# G228H.net
KiCad netlist of a schematic drawn in EAGLE
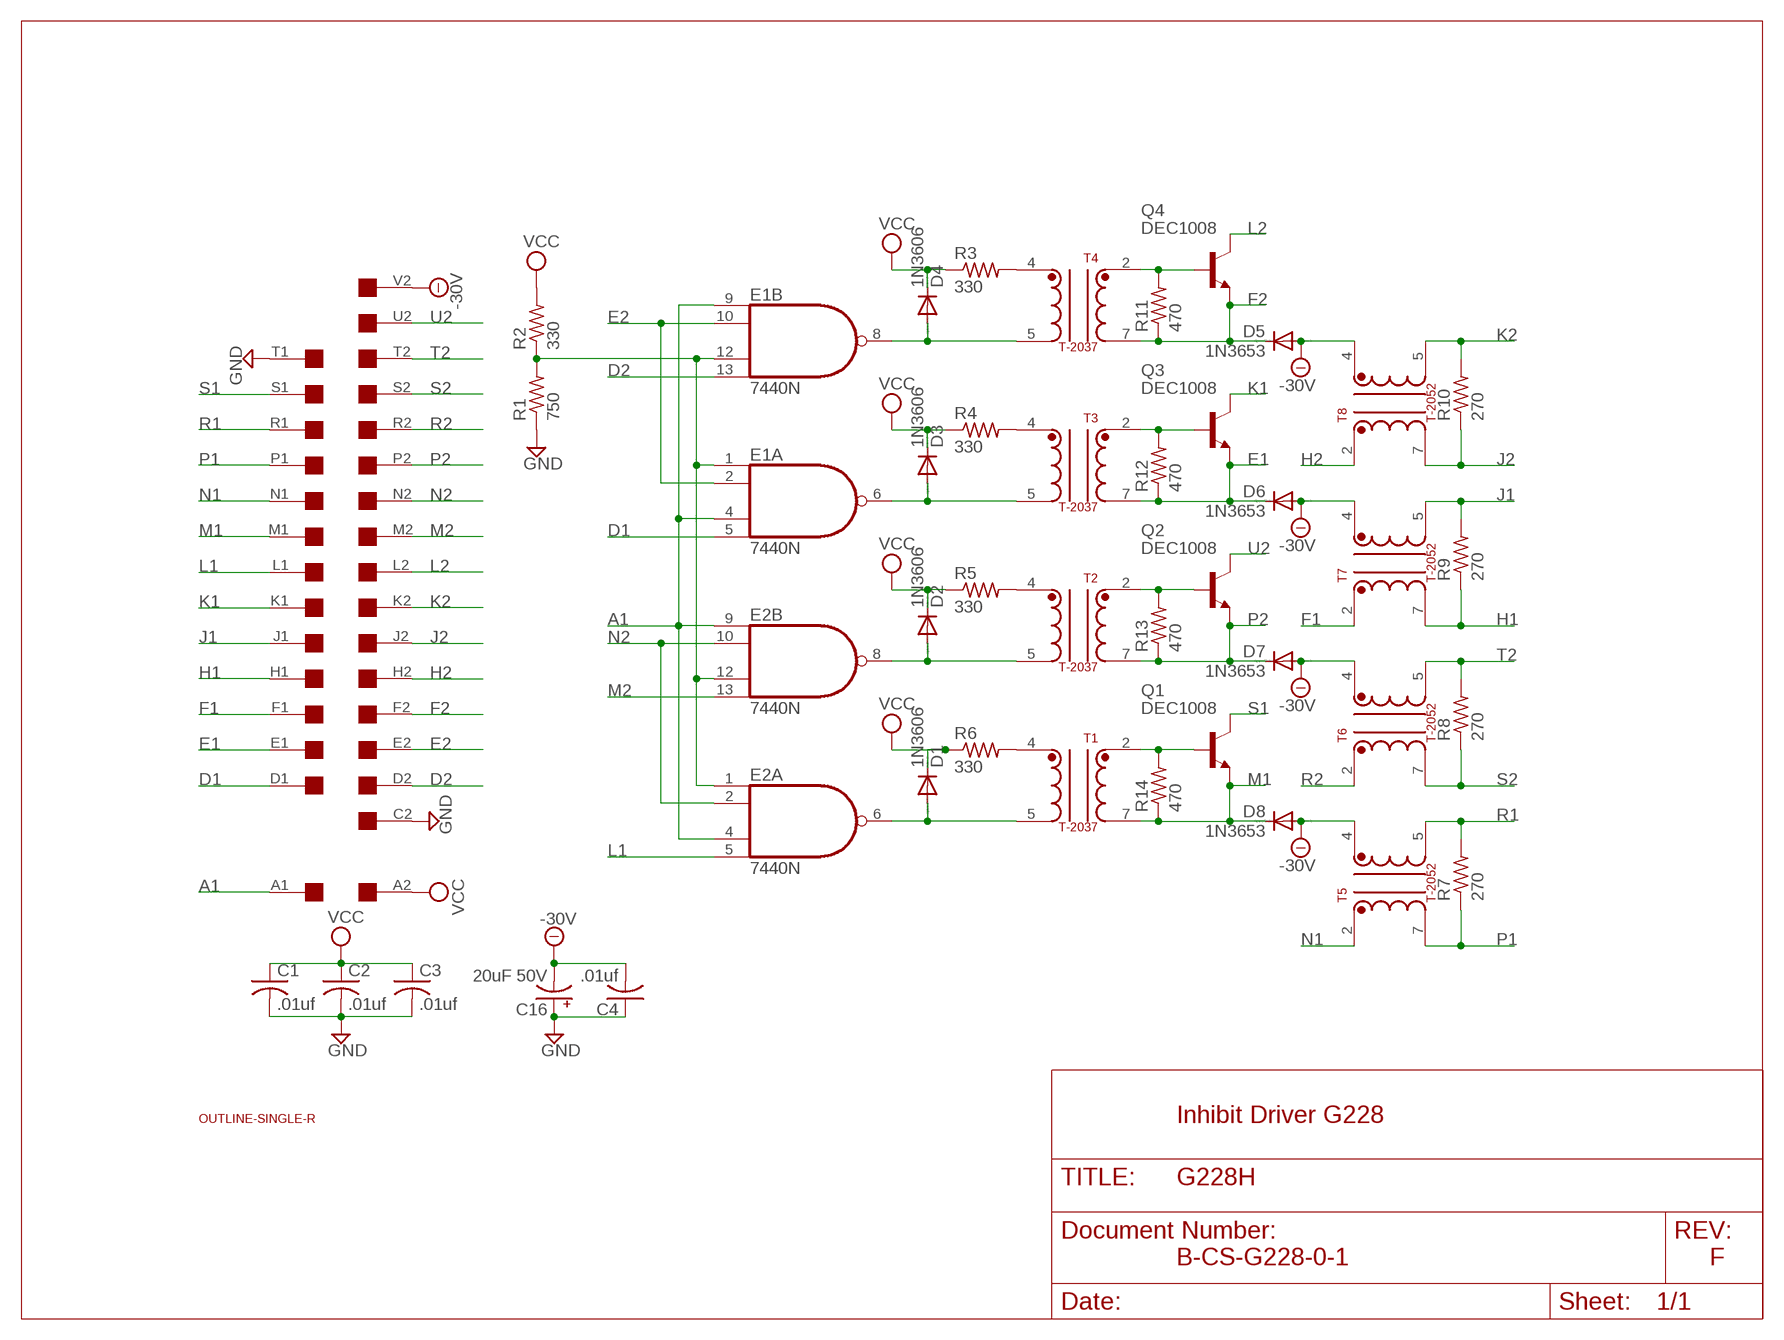
[diagram p0: schematic, sheet 1]

(export (version "E")
  (design (tool "Eeschema 10.0.6"))
  (components
    (comp (ref "C1")
      (value ".01uf")
      (footprint "eagle-import:C050-025X075")
      (libsource (lib "eagle-import") (part "C-US050-025X075"))
    )
    (comp (ref "C2")
      (value ".01uf")
      (footprint "eagle-import:C050-025X075")
      (libsource (lib "eagle-import") (part "C-US050-025X075"))
    )
    (comp (ref "C3")
      (value ".01uf")
      (footprint "eagle-import:C050-025X075")
      (libsource (lib "eagle-import") (part "C-US050-025X075"))
    )
    (comp (ref "C4")
      (value ".01uf")
      (footprint "eagle-import:C050-025X075")
      (libsource (lib "eagle-import") (part "C-US050-025X075"))
    )
    (comp (ref "C16")
      (value "20uF 50V")
      (footprint "eagle-import:E28-8")
      (libsource (lib "eagle-import") (part "CPOL-USE28-8AXIAL"))
    )
    (comp (ref "D1")
      (value "1N3606")
      (footprint "eagle-import:DO35-10")
      (libsource (lib "eagle-import") (part "1N4148DO35-10"))
    )
    (comp (ref "D2")
      (value "1N3606")
      (footprint "eagle-import:DO35-10")
      (libsource (lib "eagle-import") (part "1N4148DO35-10"))
    )
    (comp (ref "D3")
      (value "1N3606")
      (footprint "eagle-import:DO35-10")
      (libsource (lib "eagle-import") (part "1N4148DO35-10"))
    )
    (comp (ref "D4")
      (value "1N3606")
      (footprint "eagle-import:DO35-10")
      (libsource (lib "eagle-import") (part "1N4148DO35-10"))
    )
    (comp (ref "D5")
      (value "1N3653")
      (footprint "eagle-import:DO35-10")
      (libsource (lib "eagle-import") (part "1N4148DO35-10"))
    )
    (comp (ref "D6")
      (value "1N3653")
      (footprint "eagle-import:DO35-10")
      (libsource (lib "eagle-import") (part "1N4148DO35-10"))
    )
    (comp (ref "D7")
      (value "1N3653")
      (footprint "eagle-import:DO35-10")
      (libsource (lib "eagle-import") (part "1N4148DO35-10"))
    )
    (comp (ref "D8")
      (value "1N3653")
      (footprint "eagle-import:DO35-10")
      (libsource (lib "eagle-import") (part "1N4148DO35-10"))
    )
    (comp (ref "E1")
      (value "7440N")
      (footprint "eagle-import:DIL14")
      (libsource (lib "eagle-import") (part "7420NS"))
    )
    (comp (ref "E2")
      (value "7440N")
      (footprint "eagle-import:DIL14")
      (libsource (lib "eagle-import") (part "7420NS"))
    )
    (comp (ref "Q1")
      (value "DEC1008")
      (footprint "eagle-import:TO39")
      (libsource (lib "eagle-import") (part "-NPN-TO39-EBC2N1613"))
    )
    (comp (ref "Q2")
      (value "DEC1008")
      (footprint "eagle-import:TO39")
      (libsource (lib "eagle-import") (part "-NPN-TO39-EBC2N1613"))
    )
    (comp (ref "Q3")
      (value "DEC1008")
      (footprint "eagle-import:TO39")
      (libsource (lib "eagle-import") (part "-NPN-TO39-EBC2N1613"))
    )
    (comp (ref "Q4")
      (value "DEC1008")
      (footprint "eagle-import:TO39")
      (libsource (lib "eagle-import") (part "-NPN-TO39-EBC2N1613"))
    )
    (comp (ref "R1")
      (value "750")
      (footprint "eagle-import:0207_10")
      (libsource (lib "eagle-import") (part "R-US_0207/10"))
    )
    (comp (ref "R2")
      (value "330")
      (footprint "eagle-import:0207_10")
      (libsource (lib "eagle-import") (part "R-US_0207/10"))
    )
    (comp (ref "R3")
      (value "330")
      (footprint "eagle-import:0207_10")
      (libsource (lib "eagle-import") (part "R-US_0207/10"))
    )
    (comp (ref "R4")
      (value "330")
      (footprint "eagle-import:0207_10")
      (libsource (lib "eagle-import") (part "R-US_0207/10"))
    )
    (comp (ref "R5")
      (value "330")
      (footprint "eagle-import:0207_10")
      (libsource (lib "eagle-import") (part "R-US_0207/10"))
    )
    (comp (ref "R6")
      (value "330")
      (footprint "eagle-import:0207_10")
      (libsource (lib "eagle-import") (part "R-US_0207/10"))
    )
    (comp (ref "R7")
      (value "270")
      (footprint "eagle-import:0207_10")
      (libsource (lib "eagle-import") (part "R-US_0207/10"))
    )
    (comp (ref "R8")
      (value "270")
      (footprint "eagle-import:0207_10")
      (libsource (lib "eagle-import") (part "R-US_0207/10"))
    )
    (comp (ref "R9")
      (value "270")
      (footprint "eagle-import:0207_10")
      (libsource (lib "eagle-import") (part "R-US_0207/10"))
    )
    (comp (ref "R10")
      (value "270")
      (footprint "eagle-import:0207_10")
      (libsource (lib "eagle-import") (part "R-US_0207/10"))
    )
    (comp (ref "R11")
      (value "470")
      (footprint "eagle-import:0207_10")
      (libsource (lib "eagle-import") (part "R-US_0207/10"))
    )
    (comp (ref "R12")
      (value "470")
      (footprint "eagle-import:0207_10")
      (libsource (lib "eagle-import") (part "R-US_0207/10"))
    )
    (comp (ref "R13")
      (value "470")
      (footprint "eagle-import:0207_10")
      (libsource (lib "eagle-import") (part "R-US_0207/10"))
    )
    (comp (ref "R14")
      (value "470")
      (footprint "eagle-import:0207_10")
      (libsource (lib "eagle-import") (part "R-US_0207/10"))
    )
    (comp (ref "T1")
      (value "T-2037")
      (footprint "eagle-import:TRANSFORMER")
      (libsource (lib "eagle-import") (part "T-2037"))
    )
    (comp (ref "T2")
      (value "T-2037")
      (footprint "eagle-import:TRANSFORMER")
      (libsource (lib "eagle-import") (part "T-2037"))
    )
    (comp (ref "T3")
      (value "T-2037")
      (footprint "eagle-import:TRANSFORMER")
      (libsource (lib "eagle-import") (part "T-2037"))
    )
    (comp (ref "T4")
      (value "T-2037")
      (footprint "eagle-import:TRANSFORMER")
      (libsource (lib "eagle-import") (part "T-2037"))
    )
    (comp (ref "T5")
      (value "T-2052")
      (footprint "eagle-import:TRANSFORMER")
      (libsource (lib "eagle-import") (part "T-2052"))
    )
    (comp (ref "T6")
      (value "T-2052")
      (footprint "eagle-import:TRANSFORMER")
      (libsource (lib "eagle-import") (part "T-2052"))
    )
    (comp (ref "T7")
      (value "T-2052")
      (footprint "eagle-import:TRANSFORMER")
      (libsource (lib "eagle-import") (part "T-2052"))
    )
    (comp (ref "T8")
      (value "T-2052")
      (footprint "eagle-import:TRANSFORMER")
      (libsource (lib "eagle-import") (part "T-2052"))
    )
    (comp (ref "U$1")
      (value "SINGLE")
      (footprint "eagle-import:EDGE-CON2")
      (libsource (lib "eagle-import") (part "SINGLE"))
    )
    (comp (ref "U$2")
      (value "OUTLINE-SINGLE-R")
      (footprint "eagle-import:SINGLE-R")
      (libsource (lib "eagle-import") (part "OUTLINE-SINGLE-R"))
    )
  )
  (nets
    (net (code "1") (name "-30V") (class "Default")
      (node (ref "C16") (pin "-") (pinfunction "-_-") (pintype "passive"))
      (node (ref "C4") (pin "2") (pinfunction "2_2") (pintype "passive"))
      (node (ref "D5") (pin "A") (pinfunction "A_A") (pintype "passive"))
      (node (ref "D6") (pin "A") (pinfunction "A_A") (pintype "passive"))
      (node (ref "D7") (pin "A") (pinfunction "A_A") (pintype "passive"))
      (node (ref "D8") (pin "A") (pinfunction "A_A") (pintype "passive"))
      (node (ref "T5") (pin "4") (pinfunction "P$4_4") (pintype "passive"))
      (node (ref "T6") (pin "4") (pinfunction "P$4_4") (pintype "passive"))
      (node (ref "T7") (pin "4") (pinfunction "P$4_4") (pintype "passive"))
      (node (ref "T8") (pin "4") (pinfunction "P$4_4") (pintype "passive"))
      (node (ref "U$1") (pin "V2") (pinfunction "1_V2") (pintype "bidirectional"))
    )
    (net (code "2") (name "/A1") (class "Default")
      (node (ref "E1") (pin "4") (pinfunction "I2_4") (pintype "input"))
      (node (ref "E1") (pin "9") (pinfunction "I0_9") (pintype "input"))
      (node (ref "E2") (pin "4") (pinfunction "I2_4") (pintype "input"))
      (node (ref "E2") (pin "9") (pinfunction "I0_9") (pintype "input"))
      (node (ref "U$1") (pin "A1") (pinfunction "1_A1") (pintype "bidirectional"))
    )
    (net (code "3") (name "/D1") (class "Default")
      (node (ref "E1") (pin "5") (pinfunction "I3_5") (pintype "input"))
      (node (ref "U$1") (pin "D1") (pinfunction "1_D1") (pintype "bidirectional"))
    )
    (net (code "4") (name "/D2") (class "Default")
      (node (ref "E1") (pin "13") (pinfunction "I3_13") (pintype "input"))
      (node (ref "U$1") (pin "D2") (pinfunction "1_D2") (pintype "bidirectional"))
    )
    (net (code "5") (name "/E1") (class "Default")
      (node (ref "D6") (pin "C") (pinfunction "C_C") (pintype "passive"))
      (node (ref "Q3") (pin "1") (pinfunction "E_1") (pintype "passive"))
      (node (ref "R12") (pin "1") (pinfunction "1_1") (pintype "passive"))
      (node (ref "T3") (pin "7") (pinfunction "P$7_7") (pintype "passive"))
      (node (ref "U$1") (pin "E1") (pinfunction "1_E1") (pintype "bidirectional"))
    )
    (net (code "6") (name "/E2") (class "Default")
      (node (ref "E1") (pin "10") (pinfunction "I1_10") (pintype "input"))
      (node (ref "E1") (pin "2") (pinfunction "I1_2") (pintype "input"))
      (node (ref "U$1") (pin "E2") (pinfunction "1_E2") (pintype "bidirectional"))
    )
    (net (code "7") (name "/F1") (class "Default")
      (node (ref "T7") (pin "2") (pinfunction "P$2_2") (pintype "passive"))
      (node (ref "U$1") (pin "F1") (pinfunction "1_F1") (pintype "bidirectional"))
    )
    (net (code "8") (name "/F2") (class "Default")
      (node (ref "D5") (pin "C") (pinfunction "C_C") (pintype "passive"))
      (node (ref "Q4") (pin "1") (pinfunction "E_1") (pintype "passive"))
      (node (ref "R11") (pin "1") (pinfunction "1_1") (pintype "passive"))
      (node (ref "T4") (pin "7") (pinfunction "P$7_7") (pintype "passive"))
      (node (ref "U$1") (pin "F2") (pinfunction "1_F2") (pintype "bidirectional"))
    )
    (net (code "9") (name "/H1") (class "Default")
      (node (ref "R9") (pin "1") (pinfunction "1_1") (pintype "passive"))
      (node (ref "T7") (pin "7") (pinfunction "P$7_7") (pintype "passive"))
      (node (ref "U$1") (pin "H1") (pinfunction "1_H1") (pintype "bidirectional"))
    )
    (net (code "10") (name "/H2") (class "Default")
      (node (ref "T8") (pin "2") (pinfunction "P$2_2") (pintype "passive"))
      (node (ref "U$1") (pin "H2") (pinfunction "1_H2") (pintype "bidirectional"))
    )
    (net (code "11") (name "/J1") (class "Default")
      (node (ref "R9") (pin "2") (pinfunction "2_2") (pintype "passive"))
      (node (ref "T7") (pin "5") (pinfunction "P$5_5") (pintype "passive"))
      (node (ref "U$1") (pin "J1") (pinfunction "1_J1") (pintype "bidirectional"))
    )
    (net (code "12") (name "/J2") (class "Default")
      (node (ref "R10") (pin "1") (pinfunction "1_1") (pintype "passive"))
      (node (ref "T8") (pin "7") (pinfunction "P$7_7") (pintype "passive"))
      (node (ref "U$1") (pin "J2") (pinfunction "1_J2") (pintype "bidirectional"))
    )
    (net (code "13") (name "/K1") (class "Default")
      (node (ref "Q3") (pin "3") (pinfunction "C_3") (pintype "passive"))
      (node (ref "U$1") (pin "K1") (pinfunction "1_K1") (pintype "bidirectional"))
    )
    (net (code "14") (name "/K2") (class "Default")
      (node (ref "R10") (pin "2") (pinfunction "2_2") (pintype "passive"))
      (node (ref "T8") (pin "5") (pinfunction "P$5_5") (pintype "passive"))
      (node (ref "U$1") (pin "K2") (pinfunction "1_K2") (pintype "bidirectional"))
    )
    (net (code "15") (name "/L1") (class "Default")
      (node (ref "E2") (pin "5") (pinfunction "I3_5") (pintype "input"))
      (node (ref "U$1") (pin "L1") (pinfunction "1_L1") (pintype "bidirectional"))
    )
    (net (code "16") (name "/L2") (class "Default")
      (node (ref "Q4") (pin "3") (pinfunction "C_3") (pintype "passive"))
      (node (ref "U$1") (pin "L2") (pinfunction "1_L2") (pintype "bidirectional"))
    )
    (net (code "17") (name "/M1") (class "Default")
      (node (ref "D8") (pin "C") (pinfunction "C_C") (pintype "passive"))
      (node (ref "Q1") (pin "1") (pinfunction "E_1") (pintype "passive"))
      (node (ref "R14") (pin "1") (pinfunction "1_1") (pintype "passive"))
      (node (ref "T1") (pin "7") (pinfunction "P$7_7") (pintype "passive"))
      (node (ref "U$1") (pin "M1") (pinfunction "1_M1") (pintype "bidirectional"))
    )
    (net (code "18") (name "/M2") (class "Default")
      (node (ref "E2") (pin "13") (pinfunction "I3_13") (pintype "input"))
      (node (ref "U$1") (pin "M2") (pinfunction "1_M2") (pintype "bidirectional"))
    )
    (net (code "19") (name "/N1") (class "Default")
      (node (ref "T5") (pin "2") (pinfunction "P$2_2") (pintype "passive"))
      (node (ref "U$1") (pin "N1") (pinfunction "1_N1") (pintype "bidirectional"))
    )
    (net (code "20") (name "/N2") (class "Default")
      (node (ref "E2") (pin "10") (pinfunction "I1_10") (pintype "input"))
      (node (ref "E2") (pin "2") (pinfunction "I1_2") (pintype "input"))
      (node (ref "U$1") (pin "N2") (pinfunction "1_N2") (pintype "bidirectional"))
    )
    (net (code "21") (name "/P1") (class "Default")
      (node (ref "R7") (pin "1") (pinfunction "1_1") (pintype "passive"))
      (node (ref "T5") (pin "7") (pinfunction "P$7_7") (pintype "passive"))
      (node (ref "U$1") (pin "P1") (pinfunction "1_P1") (pintype "bidirectional"))
    )
    (net (code "22") (name "/P2") (class "Default")
      (node (ref "D7") (pin "C") (pinfunction "C_C") (pintype "passive"))
      (node (ref "Q2") (pin "1") (pinfunction "E_1") (pintype "passive"))
      (node (ref "R13") (pin "1") (pinfunction "1_1") (pintype "passive"))
      (node (ref "T2") (pin "7") (pinfunction "P$7_7") (pintype "passive"))
      (node (ref "U$1") (pin "P2") (pinfunction "1_P2") (pintype "bidirectional"))
    )
    (net (code "23") (name "/R1") (class "Default")
      (node (ref "R7") (pin "2") (pinfunction "2_2") (pintype "passive"))
      (node (ref "T5") (pin "5") (pinfunction "P$5_5") (pintype "passive"))
      (node (ref "U$1") (pin "R1") (pinfunction "1_R1") (pintype "bidirectional"))
    )
    (net (code "24") (name "/R2") (class "Default")
      (node (ref "T6") (pin "2") (pinfunction "P$2_2") (pintype "passive"))
      (node (ref "U$1") (pin "R2") (pinfunction "1_R2") (pintype "bidirectional"))
    )
    (net (code "25") (name "/S1") (class "Default")
      (node (ref "Q1") (pin "3") (pinfunction "C_3") (pintype "passive"))
      (node (ref "U$1") (pin "S1") (pinfunction "1_S1") (pintype "bidirectional"))
    )
    (net (code "26") (name "/S2") (class "Default")
      (node (ref "R8") (pin "1") (pinfunction "1_1") (pintype "passive"))
      (node (ref "T6") (pin "7") (pinfunction "P$7_7") (pintype "passive"))
      (node (ref "U$1") (pin "S2") (pinfunction "1_S2") (pintype "bidirectional"))
    )
    (net (code "27") (name "/T2") (class "Default")
      (node (ref "R8") (pin "2") (pinfunction "2_2") (pintype "passive"))
      (node (ref "T6") (pin "5") (pinfunction "P$5_5") (pintype "passive"))
      (node (ref "U$1") (pin "T2") (pinfunction "1_T2") (pintype "bidirectional"))
    )
    (net (code "28") (name "/U2") (class "Default")
      (node (ref "Q2") (pin "3") (pinfunction "C_3") (pintype "passive"))
      (node (ref "U$1") (pin "U2") (pinfunction "1_U2") (pintype "bidirectional"))
    )
    (net (code "29") (name "GND") (class "Default")
      (node (ref "C1") (pin "2") (pinfunction "2_2") (pintype "passive"))
      (node (ref "C16") (pin "+") (pinfunction "+_+") (pintype "passive"))
      (node (ref "C2") (pin "2") (pinfunction "2_2") (pintype "passive"))
      (node (ref "C3") (pin "2") (pinfunction "2_2") (pintype "passive"))
      (node (ref "C4") (pin "1") (pinfunction "1_1") (pintype "passive"))
      (node (ref "R1") (pin "1") (pinfunction "1_1") (pintype "passive"))
      (node (ref "U$1") (pin "C2") (pinfunction "1_C2") (pintype "bidirectional"))
      (node (ref "U$1") (pin "T1") (pinfunction "1_T1") (pintype "bidirectional"))
    )
    (net (code "30") (name "Net-(E1A-I0)") (class "Default")
      (node (ref "E1") (pin "1") (pinfunction "I0_1") (pintype "input"))
      (node (ref "E1") (pin "12") (pinfunction "I2_12") (pintype "input"))
      (node (ref "E2") (pin "1") (pinfunction "I0_1") (pintype "input"))
      (node (ref "E2") (pin "12") (pinfunction "I2_12") (pintype "input"))
      (node (ref "R1") (pin "2") (pinfunction "2_2") (pintype "passive"))
      (node (ref "R2") (pin "1") (pinfunction "1_1") (pintype "passive"))
    )
    (net (code "31") (name "Net-(E1A-O)") (class "Default")
      (node (ref "D3") (pin "A") (pinfunction "A_A") (pintype "passive"))
      (node (ref "E1") (pin "6") (pinfunction "O_6") (pintype "output"))
      (node (ref "T3") (pin "5") (pinfunction "P$5_5") (pintype "passive"))
    )
    (net (code "32") (name "Net-(E1B-O)") (class "Default")
      (node (ref "D4") (pin "A") (pinfunction "A_A") (pintype "passive"))
      (node (ref "E1") (pin "8") (pinfunction "O_8") (pintype "output"))
      (node (ref "T4") (pin "5") (pinfunction "P$5_5") (pintype "passive"))
    )
    (net (code "33") (name "Net-(E2A-O)") (class "Default")
      (node (ref "D1") (pin "A") (pinfunction "A_A") (pintype "passive"))
      (node (ref "E2") (pin "6") (pinfunction "O_6") (pintype "output"))
      (node (ref "T1") (pin "5") (pinfunction "P$5_5") (pintype "passive"))
    )
    (net (code "34") (name "Net-(E2B-O)") (class "Default")
      (node (ref "D2") (pin "A") (pinfunction "A_A") (pintype "passive"))
      (node (ref "E2") (pin "8") (pinfunction "O_8") (pintype "output"))
      (node (ref "T2") (pin "5") (pinfunction "P$5_5") (pintype "passive"))
    )
    (net (code "35") (name "Net-(Q1-B)") (class "Default")
      (node (ref "Q1") (pin "2") (pinfunction "B_2") (pintype "passive"))
      (node (ref "R14") (pin "2") (pinfunction "2_2") (pintype "passive"))
      (node (ref "T1") (pin "2") (pinfunction "P$2_2") (pintype "passive"))
    )
    (net (code "36") (name "Net-(Q2-B)") (class "Default")
      (node (ref "Q2") (pin "2") (pinfunction "B_2") (pintype "passive"))
      (node (ref "R13") (pin "2") (pinfunction "2_2") (pintype "passive"))
      (node (ref "T2") (pin "2") (pinfunction "P$2_2") (pintype "passive"))
    )
    (net (code "37") (name "Net-(Q3-B)") (class "Default")
      (node (ref "Q3") (pin "2") (pinfunction "B_2") (pintype "passive"))
      (node (ref "R12") (pin "2") (pinfunction "2_2") (pintype "passive"))
      (node (ref "T3") (pin "2") (pinfunction "P$2_2") (pintype "passive"))
    )
    (net (code "38") (name "Net-(Q4-B)") (class "Default")
      (node (ref "Q4") (pin "2") (pinfunction "B_2") (pintype "passive"))
      (node (ref "R11") (pin "2") (pinfunction "2_2") (pintype "passive"))
      (node (ref "T4") (pin "2") (pinfunction "P$2_2") (pintype "passive"))
    )
    (net (code "39") (name "Net-(T1-P$4)") (class "Default")
      (node (ref "R6") (pin "2") (pinfunction "2_2") (pintype "passive"))
      (node (ref "T1") (pin "4") (pinfunction "P$4_4") (pintype "passive"))
    )
    (net (code "40") (name "Net-(T2-P$4)") (class "Default")
      (node (ref "R5") (pin "2") (pinfunction "2_2") (pintype "passive"))
      (node (ref "T2") (pin "4") (pinfunction "P$4_4") (pintype "passive"))
    )
    (net (code "41") (name "Net-(T3-P$4)") (class "Default")
      (node (ref "R4") (pin "2") (pinfunction "2_2") (pintype "passive"))
      (node (ref "T3") (pin "4") (pinfunction "P$4_4") (pintype "passive"))
    )
    (net (code "42") (name "Net-(T4-P$4)") (class "Default")
      (node (ref "R3") (pin "2") (pinfunction "2_2") (pintype "passive"))
      (node (ref "T4") (pin "4") (pinfunction "P$4_4") (pintype "passive"))
    )
    (net (code "43") (name "VCC") (class "Default")
      (node (ref "C1") (pin "1") (pinfunction "1_1") (pintype "passive"))
      (node (ref "C2") (pin "1") (pinfunction "1_1") (pintype "passive"))
      (node (ref "C3") (pin "1") (pinfunction "1_1") (pintype "passive"))
      (node (ref "D1") (pin "C") (pinfunction "C_C") (pintype "passive"))
      (node (ref "D2") (pin "C") (pinfunction "C_C") (pintype "passive"))
      (node (ref "D3") (pin "C") (pinfunction "C_C") (pintype "passive"))
      (node (ref "D4") (pin "C") (pinfunction "C_C") (pintype "passive"))
      (node (ref "R2") (pin "2") (pinfunction "2_2") (pintype "passive"))
      (node (ref "R3") (pin "1") (pinfunction "1_1") (pintype "passive"))
      (node (ref "R4") (pin "1") (pinfunction "1_1") (pintype "passive"))
      (node (ref "R5") (pin "1") (pinfunction "1_1") (pintype "passive"))
      (node (ref "R6") (pin "1") (pinfunction "1_1") (pintype "passive"))
      (node (ref "U$1") (pin "A2") (pinfunction "1_A2") (pintype "bidirectional"))
    )
  )
)
